# stepper_driver2.net
KiCad netlist of a schematic drawn in EAGLE
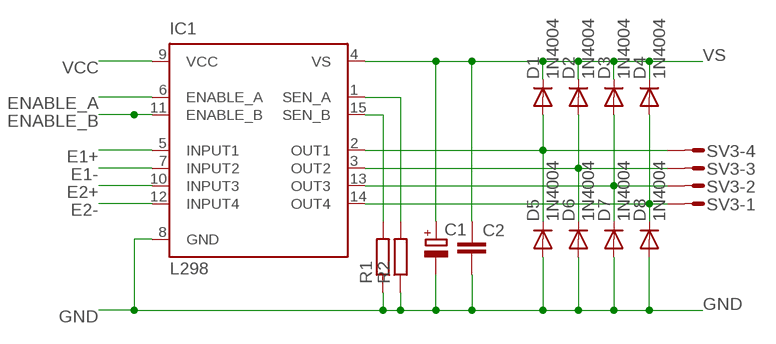
[diagram p0: schematic, sheet 1]

(export (version "E")
  (design (tool "Eeschema 10.0.6"))
  (components
    (comp (ref "C1")
      (value "CPOL-EUE3.5-10")
      (footprint "eagle-import:E3,5-10")
      (libsource (lib "eagle-import") (part "CPOL-EUE3.5-10"))
    )
    (comp (ref "C2")
      (value "C-EU050-025X075")
      (footprint "eagle-import:C050-025X075")
      (libsource (lib "eagle-import") (part "C-EU050-025X075"))
    )
    (comp (ref "D1")
      (value "1N4004")
      (footprint "eagle-import:DO41-10")
      (libsource (lib "eagle-import") (part "1N4004"))
    )
    (comp (ref "D2")
      (value "1N4004")
      (footprint "eagle-import:DO41-10")
      (libsource (lib "eagle-import") (part "1N4004"))
    )
    (comp (ref "D3")
      (value "1N4004")
      (footprint "eagle-import:DO41-10")
      (libsource (lib "eagle-import") (part "1N4004"))
    )
    (comp (ref "D4")
      (value "1N4004")
      (footprint "eagle-import:DO41-10")
      (libsource (lib "eagle-import") (part "1N4004"))
    )
    (comp (ref "D5")
      (value "1N4004")
      (footprint "eagle-import:DO41-10")
      (libsource (lib "eagle-import") (part "1N4004"))
    )
    (comp (ref "D6")
      (value "1N4004")
      (footprint "eagle-import:DO41-10")
      (libsource (lib "eagle-import") (part "1N4004"))
    )
    (comp (ref "D7")
      (value "1N4004")
      (footprint "eagle-import:DO41-10")
      (libsource (lib "eagle-import") (part "1N4004"))
    )
    (comp (ref "D8")
      (value "1N4004")
      (footprint "eagle-import:DO41-10")
      (libsource (lib "eagle-import") (part "1N4004"))
    )
    (comp (ref "IC1")
      (value "L298")
      (footprint "eagle-import:MULTIWATT-15")
      (fields (field (name "MPN") "L298N"))
      (libsource (lib "eagle-import") (part "L298"))
    )
    (comp (ref "R1")
      (value "R-EU_0207/15")
      (footprint "eagle-import:0207_15")
      (libsource (lib "eagle-import") (part "R-EU_0207/15"))
    )
    (comp (ref "R2")
      (value "R-EU_0207/15")
      (footprint "eagle-import:0207_15")
      (libsource (lib "eagle-import") (part "R-EU_0207/15"))
    )
    (comp (ref "SV3")
      (value "S04P")
      (footprint "eagle-import:S04P")
      (libsource (lib "eagle-import") (part "S04P"))
    )
  )
  (nets
    (net (code "1") (name "/E1+") (class "Default")
      (node (ref "IC1") (pin "5") (pinfunction "INPUT1_5") (pintype "input"))
    )
    (net (code "2") (name "/E1-") (class "Default")
      (node (ref "IC1") (pin "7") (pinfunction "INPUT2_7") (pintype "input"))
    )
    (net (code "3") (name "/E2+") (class "Default")
      (node (ref "IC1") (pin "10") (pinfunction "INPUT3_10") (pintype "input"))
    )
    (net (code "4") (name "/E2-") (class "Default")
      (node (ref "IC1") (pin "12") (pinfunction "INPUT4_12") (pintype "input"))
    )
    (net (code "5") (name "/ENABLE_A") (class "Default")
      (node (ref "IC1") (pin "6") (pinfunction "ENABLE_A_6") (pintype "input"))
    )
    (net (code "6") (name "/ENABLE_B") (class "Default")
      (node (ref "IC1") (pin "11") (pinfunction "ENABLE_B_11") (pintype "input"))
    )
    (net (code "7") (name "/GND") (class "Default")
      (node (ref "C1") (pin "-") (pinfunction "-_-") (pintype "passive"))
      (node (ref "C2") (pin "2") (pinfunction "2_2") (pintype "passive"))
      (node (ref "D5") (pin "A") (pinfunction "A_A") (pintype "passive"))
      (node (ref "D6") (pin "A") (pinfunction "A_A") (pintype "passive"))
      (node (ref "D7") (pin "A") (pinfunction "A_A") (pintype "passive"))
      (node (ref "D8") (pin "A") (pinfunction "A_A") (pintype "passive"))
      (node (ref "IC1") (pin "8") (pinfunction "GND_8") (pintype "power_in"))
      (node (ref "R1") (pin "1") (pinfunction "1_1") (pintype "passive"))
      (node (ref "R2") (pin "1") (pinfunction "1_1") (pintype "passive"))
    )
    (net (code "8") (name "/VCC") (class "Default")
      (node (ref "IC1") (pin "9") (pinfunction "VCC_9") (pintype "power_in"))
    )
    (net (code "9") (name "/VS") (class "Default")
      (node (ref "C1") (pin "+") (pinfunction "+_+") (pintype "passive"))
      (node (ref "C2") (pin "1") (pinfunction "1_1") (pintype "passive"))
      (node (ref "D1") (pin "C") (pinfunction "C_C") (pintype "passive"))
      (node (ref "D2") (pin "C") (pinfunction "C_C") (pintype "passive"))
      (node (ref "D3") (pin "C") (pinfunction "C_C") (pintype "passive"))
      (node (ref "D4") (pin "C") (pinfunction "C_C") (pintype "passive"))
      (node (ref "IC1") (pin "4") (pinfunction "VS_4") (pintype "power_in"))
    )
    (net (code "10") (name "Net-(IC1-OUT1)") (class "Default")
      (node (ref "D1") (pin "A") (pinfunction "A_A") (pintype "passive"))
      (node (ref "D5") (pin "C") (pinfunction "C_C") (pintype "passive"))
      (node (ref "IC1") (pin "2") (pinfunction "OUT1_2") (pintype "output"))
      (node (ref "SV3") (pin "4") (pinfunction "S_4") (pintype "passive"))
    )
    (net (code "11") (name "Net-(IC1-OUT2)") (class "Default")
      (node (ref "D2") (pin "A") (pinfunction "A_A") (pintype "passive"))
      (node (ref "D6") (pin "C") (pinfunction "C_C") (pintype "passive"))
      (node (ref "IC1") (pin "3") (pinfunction "OUT2_3") (pintype "output"))
      (node (ref "SV3") (pin "3") (pinfunction "S_3") (pintype "passive"))
    )
    (net (code "12") (name "Net-(IC1-OUT3)") (class "Default")
      (node (ref "D3") (pin "A") (pinfunction "A_A") (pintype "passive"))
      (node (ref "D7") (pin "C") (pinfunction "C_C") (pintype "passive"))
      (node (ref "IC1") (pin "13") (pinfunction "OUT3_13") (pintype "output"))
      (node (ref "SV3") (pin "2") (pinfunction "S_2") (pintype "passive"))
    )
    (net (code "13") (name "Net-(IC1-OUT4)") (class "Default")
      (node (ref "D4") (pin "A") (pinfunction "A_A") (pintype "passive"))
      (node (ref "D8") (pin "C") (pinfunction "C_C") (pintype "passive"))
      (node (ref "IC1") (pin "14") (pinfunction "OUT4_14") (pintype "output"))
      (node (ref "SV3") (pin "1") (pinfunction "S_1") (pintype "passive"))
    )
    (net (code "14") (name "Net-(IC1-SEN_A)") (class "Default")
      (node (ref "IC1") (pin "1") (pinfunction "SEN_A_1") (pintype "input"))
      (node (ref "R2") (pin "2") (pinfunction "2_2") (pintype "passive"))
    )
    (net (code "15") (name "Net-(IC1-SEN_B)") (class "Default")
      (node (ref "IC1") (pin "15") (pinfunction "SEN_B_15") (pintype "input"))
      (node (ref "R1") (pin "2") (pinfunction "2_2") (pintype "passive"))
    )
  )
)
